# schema.net
KiCad netlist of a schematic drawn in EAGLE
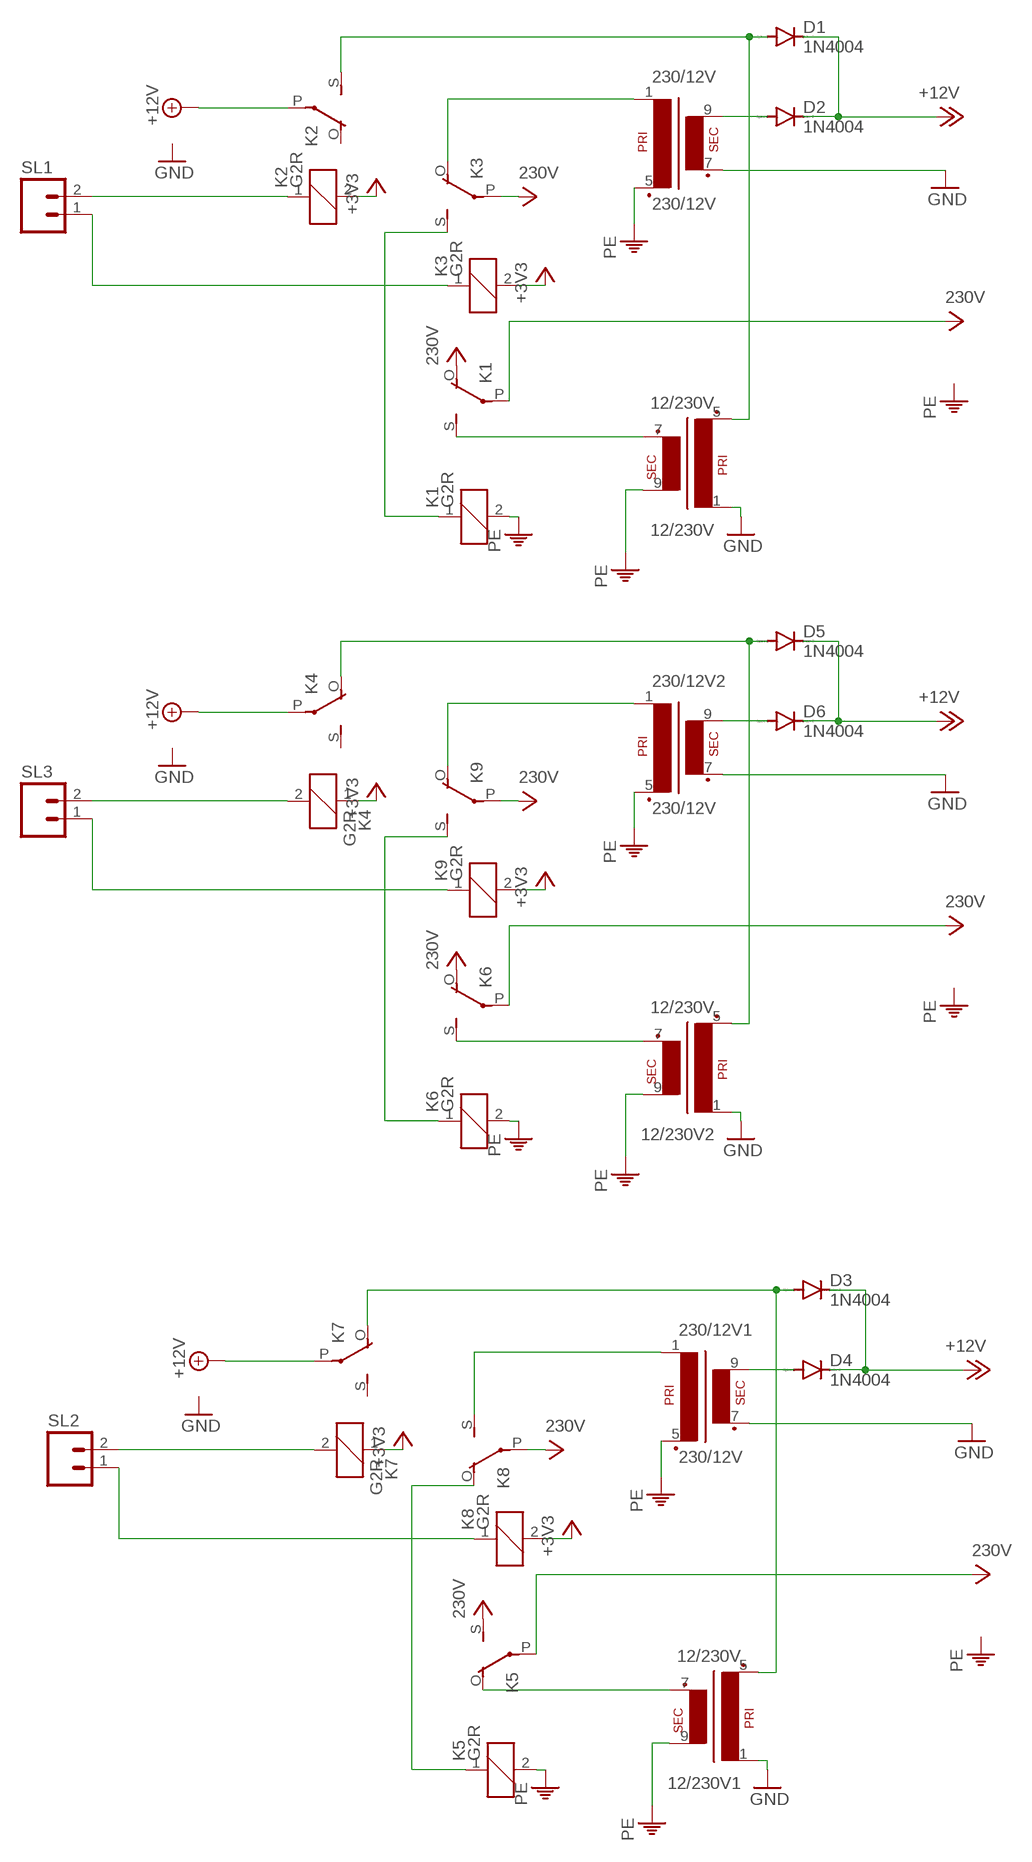
[diagram p0: schematic, sheet 1]

(export (version "E")
  (design (tool "Eeschema 10.0.6"))
  (components
    (comp (ref "12/230V")
      (value "12/230V")
      (footprint "eagle-import:EI30-1")
      (libsource (lib "eagle-import") (part "EI30-1"))
    )
    (comp (ref "12/230V1")
      (value "12/230V")
      (footprint "eagle-import:EI30-1")
      (libsource (lib "eagle-import") (part "EI30-1"))
    )
    (comp (ref "12/230V2")
      (value "12/230V")
      (footprint "eagle-import:EI30-1")
      (libsource (lib "eagle-import") (part "EI30-1"))
    )
    (comp (ref "230/12V")
      (value "230/12V")
      (footprint "eagle-import:EI30-1")
      (libsource (lib "eagle-import") (part "EI30-1"))
    )
    (comp (ref "230/12V1")
      (value "230/12V")
      (footprint "eagle-import:EI30-1")
      (libsource (lib "eagle-import") (part "EI30-1"))
    )
    (comp (ref "230/12V2")
      (value "230/12V")
      (footprint "eagle-import:EI30-1")
      (libsource (lib "eagle-import") (part "EI30-1"))
    )
    (comp (ref "D1")
      (value "1N4004")
      (footprint "eagle-import:DO41-10")
      (libsource (lib "eagle-import") (part "1N4004"))
    )
    (comp (ref "D2")
      (value "1N4004")
      (footprint "eagle-import:DO41-10")
      (libsource (lib "eagle-import") (part "1N4004"))
    )
    (comp (ref "D3")
      (value "1N4004")
      (footprint "eagle-import:DO41-10")
      (libsource (lib "eagle-import") (part "1N4004"))
    )
    (comp (ref "D4")
      (value "1N4004")
      (footprint "eagle-import:DO41-10")
      (libsource (lib "eagle-import") (part "1N4004"))
    )
    (comp (ref "D5")
      (value "1N4004")
      (footprint "eagle-import:DO41-10")
      (libsource (lib "eagle-import") (part "1N4004"))
    )
    (comp (ref "D6")
      (value "1N4004")
      (footprint "eagle-import:DO41-10")
      (libsource (lib "eagle-import") (part "1N4004"))
    )
    (comp (ref "K1")
      (value "G2R")
      (footprint "eagle-import:G2R")
      (libsource (lib "eagle-import") (part "G2R"))
    )
    (comp (ref "K2")
      (value "G2R")
      (footprint "eagle-import:G2R")
      (libsource (lib "eagle-import") (part "G2R"))
    )
    (comp (ref "K3")
      (value "G2R")
      (footprint "eagle-import:G2R")
      (libsource (lib "eagle-import") (part "G2R"))
    )
    (comp (ref "K4")
      (value "G2R")
      (footprint "eagle-import:G2R")
      (libsource (lib "eagle-import") (part "G2R"))
    )
    (comp (ref "K5")
      (value "G2R")
      (footprint "eagle-import:G2R")
      (libsource (lib "eagle-import") (part "G2R"))
    )
    (comp (ref "K6")
      (value "G2R")
      (footprint "eagle-import:G2R")
      (libsource (lib "eagle-import") (part "G2R"))
    )
    (comp (ref "K7")
      (value "G2R")
      (footprint "eagle-import:G2R")
      (libsource (lib "eagle-import") (part "G2R"))
    )
    (comp (ref "K8")
      (value "G2R")
      (footprint "eagle-import:G2R")
      (libsource (lib "eagle-import") (part "G2R"))
    )
    (comp (ref "K9")
      (value "G2R")
      (footprint "eagle-import:G2R")
      (libsource (lib "eagle-import") (part "G2R"))
    )
    (comp (ref "SL1")
      (value "M02")
      (footprint "eagle-import:02P")
      (libsource (lib "eagle-import") (part "M02"))
    )
    (comp (ref "SL2")
      (value "M02")
      (footprint "eagle-import:02P")
      (libsource (lib "eagle-import") (part "M02"))
    )
    (comp (ref "SL3")
      (value "M02")
      (footprint "eagle-import:02P")
      (libsource (lib "eagle-import") (part "M02"))
    )
  )
  (nets
    (net (code "1") (name "+3V3") (class "Default")
      (node (ref "K2") (pin "2") (pinfunction "2_2") (pintype "passive"))
      (node (ref "K3") (pin "2") (pinfunction "2_2") (pintype "passive"))
      (node (ref "K4") (pin "1") (pinfunction "1_1") (pintype "passive"))
      (node (ref "K7") (pin "1") (pinfunction "1_1") (pintype "passive"))
      (node (ref "K8") (pin "2") (pinfunction "2_2") (pintype "passive"))
      (node (ref "K9") (pin "2") (pinfunction "2_2") (pintype "passive"))
    )
    (net (code "2") (name "+12V") (class "Default")
      (node (ref "D1") (pin "C") (pinfunction "C_C") (pintype "passive"))
      (node (ref "D2") (pin "C") (pinfunction "C_C") (pintype "passive"))
      (node (ref "D3") (pin "C") (pinfunction "C_C") (pintype "passive"))
      (node (ref "D4") (pin "C") (pinfunction "C_C") (pintype "passive"))
      (node (ref "D5") (pin "C") (pinfunction "C_C") (pintype "passive"))
      (node (ref "D6") (pin "C") (pinfunction "C_C") (pintype "passive"))
      (node (ref "K2") (pin "P") (pinfunction "P_P") (pintype "passive"))
      (node (ref "K4") (pin "P") (pinfunction "P_P") (pintype "passive"))
      (node (ref "K7") (pin "P") (pinfunction "P_P") (pintype "passive"))
    )
    (net (code "3") (name "230V") (class "Default")
      (node (ref "K1") (pin "O") (pinfunction "O_O") (pintype "passive"))
      (node (ref "K1") (pin "P") (pinfunction "P_P") (pintype "passive"))
      (node (ref "K3") (pin "P") (pinfunction "P_P") (pintype "passive"))
      (node (ref "K5") (pin "P") (pinfunction "P_P") (pintype "passive"))
      (node (ref "K5") (pin "S") (pinfunction "S_S") (pintype "passive"))
      (node (ref "K6") (pin "O") (pinfunction "O_O") (pintype "passive"))
      (node (ref "K6") (pin "P") (pinfunction "P_P") (pintype "passive"))
      (node (ref "K8") (pin "P") (pinfunction "P_P") (pintype "passive"))
      (node (ref "K9") (pin "P") (pinfunction "P_P") (pintype "passive"))
    )
    (net (code "4") (name "GND") (class "Default")
      (node (ref "12/230V") (pin "1") (pinfunction "P1_1") (pintype "passive"))
      (node (ref "12/230V1") (pin "1") (pinfunction "P1_1") (pintype "passive"))
      (node (ref "12/230V2") (pin "1") (pinfunction "P1_1") (pintype "passive"))
      (node (ref "230/12V") (pin "7") (pinfunction "S3_7") (pintype "passive"))
      (node (ref "230/12V1") (pin "7") (pinfunction "S3_7") (pintype "passive"))
      (node (ref "230/12V2") (pin "7") (pinfunction "S3_7") (pintype "passive"))
    )
    (net (code "5") (name "Net-(12/230V-P2)") (class "Default")
      (node (ref "12/230V") (pin "5") (pinfunction "P2_5") (pintype "passive"))
      (node (ref "D1") (pin "A") (pinfunction "A_A") (pintype "passive"))
      (node (ref "K2") (pin "S") (pinfunction "S_S") (pintype "passive"))
    )
    (net (code "6") (name "Net-(12/230V-S3)") (class "Default")
      (node (ref "12/230V") (pin "7") (pinfunction "S3_7") (pintype "passive"))
      (node (ref "K1") (pin "S") (pinfunction "S_S") (pintype "passive"))
    )
    (net (code "7") (name "Net-(12/230V1-P2)") (class "Default")
      (node (ref "12/230V1") (pin "5") (pinfunction "P2_5") (pintype "passive"))
      (node (ref "D3") (pin "A") (pinfunction "A_A") (pintype "passive"))
      (node (ref "K7") (pin "O") (pinfunction "O_O") (pintype "passive"))
    )
    (net (code "8") (name "Net-(12/230V1-S3)") (class "Default")
      (node (ref "12/230V1") (pin "7") (pinfunction "S3_7") (pintype "passive"))
      (node (ref "K5") (pin "O") (pinfunction "O_O") (pintype "passive"))
    )
    (net (code "9") (name "Net-(12/230V2-P2)") (class "Default")
      (node (ref "12/230V2") (pin "5") (pinfunction "P2_5") (pintype "passive"))
      (node (ref "D5") (pin "A") (pinfunction "A_A") (pintype "passive"))
      (node (ref "K4") (pin "O") (pinfunction "O_O") (pintype "passive"))
    )
    (net (code "10") (name "Net-(12/230V2-S3)") (class "Default")
      (node (ref "12/230V2") (pin "7") (pinfunction "S3_7") (pintype "passive"))
      (node (ref "K6") (pin "S") (pinfunction "S_S") (pintype "passive"))
    )
    (net (code "11") (name "Net-(230/12V-P1)") (class "Default")
      (node (ref "230/12V") (pin "1") (pinfunction "P1_1") (pintype "passive"))
      (node (ref "K3") (pin "O") (pinfunction "O_O") (pintype "passive"))
    )
    (net (code "12") (name "Net-(230/12V-S4)") (class "Default")
      (node (ref "230/12V") (pin "9") (pinfunction "S4_9") (pintype "passive"))
      (node (ref "D2") (pin "A") (pinfunction "A_A") (pintype "passive"))
    )
    (net (code "13") (name "Net-(230/12V1-P1)") (class "Default")
      (node (ref "230/12V1") (pin "1") (pinfunction "P1_1") (pintype "passive"))
      (node (ref "K8") (pin "S") (pinfunction "S_S") (pintype "passive"))
    )
    (net (code "14") (name "Net-(230/12V1-S4)") (class "Default")
      (node (ref "230/12V1") (pin "9") (pinfunction "S4_9") (pintype "passive"))
      (node (ref "D4") (pin "A") (pinfunction "A_A") (pintype "passive"))
    )
    (net (code "15") (name "Net-(230/12V2-P1)") (class "Default")
      (node (ref "230/12V2") (pin "1") (pinfunction "P1_1") (pintype "passive"))
      (node (ref "K9") (pin "O") (pinfunction "O_O") (pintype "passive"))
    )
    (net (code "16") (name "Net-(230/12V2-S4)") (class "Default")
      (node (ref "230/12V2") (pin "9") (pinfunction "S4_9") (pintype "passive"))
      (node (ref "D6") (pin "A") (pinfunction "A_A") (pintype "passive"))
    )
    (net (code "17") (name "Net-(K1-Pad1)") (class "Default")
      (node (ref "K1") (pin "1") (pinfunction "1_1") (pintype "passive"))
      (node (ref "K3") (pin "S") (pinfunction "S_S") (pintype "passive"))
    )
    (net (code "18") (name "Net-(K2-Pad1)") (class "Default")
      (node (ref "K2") (pin "1") (pinfunction "1_1") (pintype "passive"))
      (node (ref "SL1") (pin "2") (pinfunction "2_2") (pintype "passive"))
    )
    (net (code "19") (name "Net-(K3-Pad1)") (class "Default")
      (node (ref "K3") (pin "1") (pinfunction "1_1") (pintype "passive"))
      (node (ref "SL1") (pin "1") (pinfunction "1_1") (pintype "passive"))
    )
    (net (code "20") (name "Net-(K4-Pad2)") (class "Default")
      (node (ref "K4") (pin "2") (pinfunction "2_2") (pintype "passive"))
      (node (ref "SL3") (pin "2") (pinfunction "2_2") (pintype "passive"))
    )
    (net (code "21") (name "Net-(K5-Pad1)") (class "Default")
      (node (ref "K5") (pin "1") (pinfunction "1_1") (pintype "passive"))
      (node (ref "K8") (pin "O") (pinfunction "O_O") (pintype "passive"))
    )
    (net (code "22") (name "Net-(K6-Pad1)") (class "Default")
      (node (ref "K6") (pin "1") (pinfunction "1_1") (pintype "passive"))
      (node (ref "K9") (pin "S") (pinfunction "S_S") (pintype "passive"))
    )
    (net (code "23") (name "Net-(K7-Pad2)") (class "Default")
      (node (ref "K7") (pin "2") (pinfunction "2_2") (pintype "passive"))
      (node (ref "SL2") (pin "2") (pinfunction "2_2") (pintype "passive"))
    )
    (net (code "24") (name "Net-(K8-Pad1)") (class "Default")
      (node (ref "K8") (pin "1") (pinfunction "1_1") (pintype "passive"))
      (node (ref "SL2") (pin "1") (pinfunction "1_1") (pintype "passive"))
    )
    (net (code "25") (name "Net-(K9-Pad1)") (class "Default")
      (node (ref "K9") (pin "1") (pinfunction "1_1") (pintype "passive"))
      (node (ref "SL3") (pin "1") (pinfunction "1_1") (pintype "passive"))
    )
    (net (code "26") (name "PE") (class "Default")
      (node (ref "12/230V") (pin "9") (pinfunction "S4_9") (pintype "passive"))
      (node (ref "12/230V1") (pin "9") (pinfunction "S4_9") (pintype "passive"))
      (node (ref "12/230V2") (pin "9") (pinfunction "S4_9") (pintype "passive"))
      (node (ref "230/12V") (pin "5") (pinfunction "P2_5") (pintype "passive"))
      (node (ref "230/12V1") (pin "5") (pinfunction "P2_5") (pintype "passive"))
      (node (ref "230/12V2") (pin "5") (pinfunction "P2_5") (pintype "passive"))
      (node (ref "K1") (pin "2") (pinfunction "2_2") (pintype "passive"))
      (node (ref "K5") (pin "2") (pinfunction "2_2") (pintype "passive"))
      (node (ref "K6") (pin "2") (pinfunction "2_2") (pintype "passive"))
    )
    (net (code "27") (name "unconnected-(K2-PadO)") (class "Default")
      (node (ref "K2") (pin "O") (pinfunction "O_O") (pintype "passive"))
    )
    (net (code "28") (name "unconnected-(K4-PadS)") (class "Default")
      (node (ref "K4") (pin "S") (pinfunction "S_S") (pintype "passive"))
    )
    (net (code "29") (name "unconnected-(K7-PadS)") (class "Default")
      (node (ref "K7") (pin "S") (pinfunction "S_S") (pintype "passive"))
    )
  )
)
